# gpio_connector.net
KiCad netlist of a schematic drawn in EAGLE
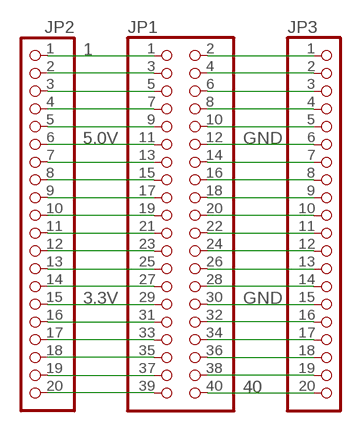
[diagram p0: schematic, sheet 1]

(export (version "E")
  (design (tool "Eeschema 10.0.6"))
  (components
    (comp (ref "JP1")
      (value "PINHD-2X20")
      (footprint "eagle-import:2X20")
      (libsource (lib "eagle-import") (part "PINHD-2X20"))
    )
    (comp (ref "JP2")
      (value "PINHD-1X20")
      (footprint "eagle-import:1X20")
      (libsource (lib "eagle-import") (part "PINHD-1X20"))
    )
    (comp (ref "JP3")
      (value "PINHD-1X20")
      (footprint "eagle-import:1X20")
      (libsource (lib "eagle-import") (part "PINHD-1X20"))
    )
  )
  (nets
    (net (code "1") (name "/1") (class "Default")
      (node (ref "JP1") (pin "1") (pinfunction "1_1") (pintype "passive"))
      (node (ref "JP2") (pin "1") (pinfunction "1_1") (pintype "passive"))
    )
    (net (code "2") (name "/3.3V") (class "Default")
      (node (ref "JP1") (pin "29") (pinfunction "29_29") (pintype "passive"))
      (node (ref "JP2") (pin "15") (pinfunction "15_15") (pintype "passive"))
    )
    (net (code "3") (name "/5.0V") (class "Default")
      (node (ref "JP1") (pin "11") (pinfunction "11_11") (pintype "passive"))
      (node (ref "JP2") (pin "6") (pinfunction "6_6") (pintype "passive"))
    )
    (net (code "4") (name "/40") (class "Default")
      (node (ref "JP1") (pin "40") (pinfunction "40_40") (pintype "passive"))
      (node (ref "JP3") (pin "20") (pinfunction "20_20") (pintype "passive"))
    )
    (net (code "5") (name "/GND") (class "Default")
      (node (ref "JP1") (pin "12") (pinfunction "12_12") (pintype "passive"))
      (node (ref "JP1") (pin "30") (pinfunction "30_30") (pintype "passive"))
      (node (ref "JP3") (pin "15") (pinfunction "15_15") (pintype "passive"))
      (node (ref "JP3") (pin "6") (pinfunction "6_6") (pintype "passive"))
    )
    (net (code "6") (name "Net-(JP1-Pad2)") (class "Default")
      (node (ref "JP1") (pin "2") (pinfunction "2_2") (pintype "passive"))
      (node (ref "JP3") (pin "1") (pinfunction "1_1") (pintype "passive"))
    )
    (net (code "7") (name "Net-(JP1-Pad3)") (class "Default")
      (node (ref "JP1") (pin "3") (pinfunction "3_3") (pintype "passive"))
      (node (ref "JP2") (pin "2") (pinfunction "2_2") (pintype "passive"))
    )
    (net (code "8") (name "Net-(JP1-Pad4)") (class "Default")
      (node (ref "JP1") (pin "4") (pinfunction "4_4") (pintype "passive"))
      (node (ref "JP3") (pin "2") (pinfunction "2_2") (pintype "passive"))
    )
    (net (code "9") (name "Net-(JP1-Pad5)") (class "Default")
      (node (ref "JP1") (pin "5") (pinfunction "5_5") (pintype "passive"))
      (node (ref "JP2") (pin "3") (pinfunction "3_3") (pintype "passive"))
    )
    (net (code "10") (name "Net-(JP1-Pad6)") (class "Default")
      (node (ref "JP1") (pin "6") (pinfunction "6_6") (pintype "passive"))
      (node (ref "JP3") (pin "3") (pinfunction "3_3") (pintype "passive"))
    )
    (net (code "11") (name "Net-(JP1-Pad7)") (class "Default")
      (node (ref "JP1") (pin "7") (pinfunction "7_7") (pintype "passive"))
      (node (ref "JP2") (pin "4") (pinfunction "4_4") (pintype "passive"))
    )
    (net (code "12") (name "Net-(JP1-Pad8)") (class "Default")
      (node (ref "JP1") (pin "8") (pinfunction "8_8") (pintype "passive"))
      (node (ref "JP3") (pin "4") (pinfunction "4_4") (pintype "passive"))
    )
    (net (code "13") (name "Net-(JP1-Pad9)") (class "Default")
      (node (ref "JP1") (pin "9") (pinfunction "9_9") (pintype "passive"))
      (node (ref "JP2") (pin "5") (pinfunction "5_5") (pintype "passive"))
    )
    (net (code "14") (name "Net-(JP1-Pad10)") (class "Default")
      (node (ref "JP1") (pin "10") (pinfunction "10_10") (pintype "passive"))
      (node (ref "JP3") (pin "5") (pinfunction "5_5") (pintype "passive"))
    )
    (net (code "15") (name "Net-(JP1-Pad13)") (class "Default")
      (node (ref "JP1") (pin "13") (pinfunction "13_13") (pintype "passive"))
      (node (ref "JP2") (pin "7") (pinfunction "7_7") (pintype "passive"))
    )
    (net (code "16") (name "Net-(JP1-Pad14)") (class "Default")
      (node (ref "JP1") (pin "14") (pinfunction "14_14") (pintype "passive"))
      (node (ref "JP3") (pin "7") (pinfunction "7_7") (pintype "passive"))
    )
    (net (code "17") (name "Net-(JP1-Pad15)") (class "Default")
      (node (ref "JP1") (pin "15") (pinfunction "15_15") (pintype "passive"))
      (node (ref "JP2") (pin "8") (pinfunction "8_8") (pintype "passive"))
    )
    (net (code "18") (name "Net-(JP1-Pad16)") (class "Default")
      (node (ref "JP1") (pin "16") (pinfunction "16_16") (pintype "passive"))
      (node (ref "JP3") (pin "8") (pinfunction "8_8") (pintype "passive"))
    )
    (net (code "19") (name "Net-(JP1-Pad17)") (class "Default")
      (node (ref "JP1") (pin "17") (pinfunction "17_17") (pintype "passive"))
      (node (ref "JP2") (pin "9") (pinfunction "9_9") (pintype "passive"))
    )
    (net (code "20") (name "Net-(JP1-Pad18)") (class "Default")
      (node (ref "JP1") (pin "18") (pinfunction "18_18") (pintype "passive"))
      (node (ref "JP3") (pin "9") (pinfunction "9_9") (pintype "passive"))
    )
    (net (code "21") (name "Net-(JP1-Pad19)") (class "Default")
      (node (ref "JP1") (pin "19") (pinfunction "19_19") (pintype "passive"))
      (node (ref "JP2") (pin "10") (pinfunction "10_10") (pintype "passive"))
    )
    (net (code "22") (name "Net-(JP1-Pad20)") (class "Default")
      (node (ref "JP1") (pin "20") (pinfunction "20_20") (pintype "passive"))
      (node (ref "JP3") (pin "10") (pinfunction "10_10") (pintype "passive"))
    )
    (net (code "23") (name "Net-(JP1-Pad21)") (class "Default")
      (node (ref "JP1") (pin "21") (pinfunction "21_21") (pintype "passive"))
      (node (ref "JP2") (pin "11") (pinfunction "11_11") (pintype "passive"))
    )
    (net (code "24") (name "Net-(JP1-Pad22)") (class "Default")
      (node (ref "JP1") (pin "22") (pinfunction "22_22") (pintype "passive"))
      (node (ref "JP3") (pin "11") (pinfunction "11_11") (pintype "passive"))
    )
    (net (code "25") (name "Net-(JP1-Pad23)") (class "Default")
      (node (ref "JP1") (pin "23") (pinfunction "23_23") (pintype "passive"))
      (node (ref "JP2") (pin "12") (pinfunction "12_12") (pintype "passive"))
    )
    (net (code "26") (name "Net-(JP1-Pad24)") (class "Default")
      (node (ref "JP1") (pin "24") (pinfunction "24_24") (pintype "passive"))
      (node (ref "JP3") (pin "12") (pinfunction "12_12") (pintype "passive"))
    )
    (net (code "27") (name "Net-(JP1-Pad25)") (class "Default")
      (node (ref "JP1") (pin "25") (pinfunction "25_25") (pintype "passive"))
      (node (ref "JP2") (pin "13") (pinfunction "13_13") (pintype "passive"))
    )
    (net (code "28") (name "Net-(JP1-Pad26)") (class "Default")
      (node (ref "JP1") (pin "26") (pinfunction "26_26") (pintype "passive"))
      (node (ref "JP3") (pin "13") (pinfunction "13_13") (pintype "passive"))
    )
    (net (code "29") (name "Net-(JP1-Pad27)") (class "Default")
      (node (ref "JP1") (pin "27") (pinfunction "27_27") (pintype "passive"))
      (node (ref "JP2") (pin "14") (pinfunction "14_14") (pintype "passive"))
    )
    (net (code "30") (name "Net-(JP1-Pad28)") (class "Default")
      (node (ref "JP1") (pin "28") (pinfunction "28_28") (pintype "passive"))
      (node (ref "JP3") (pin "14") (pinfunction "14_14") (pintype "passive"))
    )
    (net (code "31") (name "Net-(JP1-Pad31)") (class "Default")
      (node (ref "JP1") (pin "31") (pinfunction "31_31") (pintype "passive"))
      (node (ref "JP2") (pin "16") (pinfunction "16_16") (pintype "passive"))
    )
    (net (code "32") (name "Net-(JP1-Pad32)") (class "Default")
      (node (ref "JP1") (pin "32") (pinfunction "32_32") (pintype "passive"))
      (node (ref "JP3") (pin "16") (pinfunction "16_16") (pintype "passive"))
    )
    (net (code "33") (name "Net-(JP1-Pad33)") (class "Default")
      (node (ref "JP1") (pin "33") (pinfunction "33_33") (pintype "passive"))
      (node (ref "JP2") (pin "17") (pinfunction "17_17") (pintype "passive"))
    )
    (net (code "34") (name "Net-(JP1-Pad34)") (class "Default")
      (node (ref "JP1") (pin "34") (pinfunction "34_34") (pintype "passive"))
      (node (ref "JP3") (pin "17") (pinfunction "17_17") (pintype "passive"))
    )
    (net (code "35") (name "Net-(JP1-Pad35)") (class "Default")
      (node (ref "JP1") (pin "35") (pinfunction "35_35") (pintype "passive"))
      (node (ref "JP2") (pin "18") (pinfunction "18_18") (pintype "passive"))
    )
    (net (code "36") (name "Net-(JP1-Pad36)") (class "Default")
      (node (ref "JP1") (pin "36") (pinfunction "36_36") (pintype "passive"))
      (node (ref "JP3") (pin "18") (pinfunction "18_18") (pintype "passive"))
    )
    (net (code "37") (name "Net-(JP1-Pad37)") (class "Default")
      (node (ref "JP1") (pin "37") (pinfunction "37_37") (pintype "passive"))
      (node (ref "JP2") (pin "19") (pinfunction "19_19") (pintype "passive"))
    )
    (net (code "38") (name "Net-(JP1-Pad38)") (class "Default")
      (node (ref "JP1") (pin "38") (pinfunction "38_38") (pintype "passive"))
      (node (ref "JP3") (pin "19") (pinfunction "19_19") (pintype "passive"))
    )
    (net (code "39") (name "Net-(JP1-Pad39)") (class "Default")
      (node (ref "JP1") (pin "39") (pinfunction "39_39") (pintype "passive"))
      (node (ref "JP2") (pin "20") (pinfunction "20_20") (pintype "passive"))
    )
  )
)
